# Connector_Board.net
KiCad netlist of a schematic drawn in Altium Designer
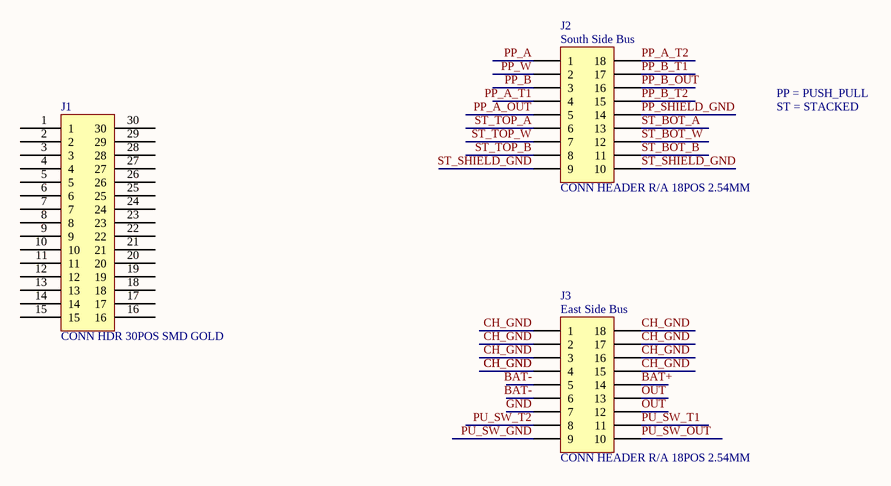
[diagram p0: Connector_Board.SchDoc]

(export (version "E")
  (design (tool "Eeschema 10.0.6"))
  (components
    (comp (ref "J1")
      (value "CONN HDR 30POS SMD GOLD")
      (footprint "DF12(3.0)-30DP")
      (description "30 Position Connector Header, Outer Shroud Contacts Surface Mount Gold")
      (fields (field (name "MANUFACTURER") "Hirose") (field (name "DIGIKEY PART NUMBER") "H11703CT-ND"))
      (libsource (lib "GuitarLibrary") (part "DF12(3.0)-30DP-0.5V(86)"))
    )
    (comp (ref "J2")
      (value "CONN HEADER R/A 18POS 2.54MM")
      (footprint "CONN HEADER R/A 18POS 2.54MM")
      (description "Connector Header Through Hole, Right Angle 18 position 0.100\" (2.54mm)")
      (fields
        (field (name "MANUFACTURER") "Samtec Inc.")
        (field (name "DIGIKEY PART NUMBER") "SAM1041-09-ND")
      )
      (libsource (lib "GuitarLibrary") (part "CONN HEADER R/A 18POS 2.54MM"))
    )
    (comp (ref "J3")
      (value "CONN HEADER R/A 18POS 2.54MM")
      (footprint "CONN HEADER R/A 18POS 2.54MM")
      (description "Connector Header Through Hole, Right Angle 18 position 0.100\" (2.54mm)")
      (fields
        (field (name "MANUFACTURER") "Samtec Inc.")
        (field (name "DIGIKEY PART NUMBER") "SAM1041-09-ND")
      )
      (libsource (lib "GuitarLibrary") (part "CONN HEADER R/A 18POS 2.54MM"))
    )
  )
  (nets
    (net (code "1") (name "/BAT+") (class "Default")
      (node (ref "J3") (pin "14") (pinfunction "14_14") (pintype "passive"))
    )
    (net (code "2") (name "/BAT-") (class "Default")
      (node (ref "J3") (pin "5") (pinfunction "5_5") (pintype "passive"))
      (node (ref "J3") (pin "6") (pinfunction "6_6") (pintype "passive"))
    )
    (net (code "3") (name "/CH_GND") (class "Default")
      (node (ref "J3") (pin "1") (pinfunction "1_1") (pintype "passive"))
      (node (ref "J3") (pin "15") (pinfunction "15_15") (pintype "passive"))
      (node (ref "J3") (pin "16") (pinfunction "16_16") (pintype "passive"))
      (node (ref "J3") (pin "17") (pinfunction "17_17") (pintype "passive"))
      (node (ref "J3") (pin "18") (pinfunction "18_18") (pintype "passive"))
      (node (ref "J3") (pin "2") (pinfunction "2_2") (pintype "passive"))
      (node (ref "J3") (pin "3") (pinfunction "3_3") (pintype "passive"))
      (node (ref "J3") (pin "4") (pinfunction "4_4") (pintype "passive"))
    )
    (net (code "4") (name "/GND") (class "Default")
      (node (ref "J3") (pin "7") (pinfunction "7_7") (pintype "passive"))
    )
    (net (code "5") (name "/OUT") (class "Default")
      (node (ref "J3") (pin "12") (pinfunction "12_12") (pintype "passive"))
      (node (ref "J3") (pin "13") (pinfunction "13_13") (pintype "passive"))
    )
    (net (code "6") (name "/PP_A") (class "Default")
      (node (ref "J2") (pin "1") (pinfunction "1_1") (pintype "passive"))
    )
    (net (code "7") (name "/PP_A_OUT") (class "Default")
      (node (ref "J2") (pin "5") (pinfunction "5_5") (pintype "passive"))
    )
    (net (code "8") (name "/PP_A_T1") (class "Default")
      (node (ref "J2") (pin "4") (pinfunction "4_4") (pintype "passive"))
    )
    (net (code "9") (name "/PP_A_T2") (class "Default")
      (node (ref "J2") (pin "18") (pinfunction "18_18") (pintype "passive"))
    )
    (net (code "10") (name "/PP_B") (class "Default")
      (node (ref "J2") (pin "3") (pinfunction "3_3") (pintype "passive"))
    )
    (net (code "11") (name "/PP_B_OUT") (class "Default")
      (node (ref "J2") (pin "16") (pinfunction "16_16") (pintype "passive"))
    )
    (net (code "12") (name "/PP_B_T1") (class "Default")
      (node (ref "J2") (pin "17") (pinfunction "17_17") (pintype "passive"))
    )
    (net (code "13") (name "/PP_B_T2") (class "Default")
      (node (ref "J2") (pin "15") (pinfunction "15_15") (pintype "passive"))
    )
    (net (code "14") (name "/PP_SHIELD_GND") (class "Default")
      (node (ref "J2") (pin "14") (pinfunction "14_14") (pintype "passive"))
    )
    (net (code "15") (name "/PP_W") (class "Default")
      (node (ref "J2") (pin "2") (pinfunction "2_2") (pintype "passive"))
    )
    (net (code "16") (name "/PU_SW_GND") (class "Default")
      (node (ref "J3") (pin "9") (pinfunction "9_9") (pintype "passive"))
    )
    (net (code "17") (name "/PU_SW_OUT") (class "Default")
      (node (ref "J3") (pin "10") (pinfunction "10_10") (pintype "passive"))
    )
    (net (code "18") (name "/PU_SW_T1") (class "Default")
      (node (ref "J3") (pin "11") (pinfunction "11_11") (pintype "passive"))
    )
    (net (code "19") (name "/PU_SW_T2") (class "Default")
      (node (ref "J3") (pin "8") (pinfunction "8_8") (pintype "passive"))
    )
    (net (code "20") (name "/ST_BOT_A") (class "Default")
      (node (ref "J2") (pin "13") (pinfunction "13_13") (pintype "passive"))
    )
    (net (code "21") (name "/ST_BOT_B") (class "Default")
      (node (ref "J2") (pin "11") (pinfunction "11_11") (pintype "passive"))
    )
    (net (code "22") (name "/ST_BOT_W") (class "Default")
      (node (ref "J2") (pin "12") (pinfunction "12_12") (pintype "passive"))
    )
    (net (code "23") (name "/ST_SHIELD_GND") (class "Default")
      (node (ref "J2") (pin "10") (pinfunction "10_10") (pintype "passive"))
      (node (ref "J2") (pin "9") (pinfunction "9_9") (pintype "passive"))
    )
    (net (code "24") (name "/ST_TOP_A") (class "Default")
      (node (ref "J2") (pin "6") (pinfunction "6_6") (pintype "passive"))
    )
    (net (code "25") (name "/ST_TOP_B") (class "Default")
      (node (ref "J2") (pin "8") (pinfunction "8_8") (pintype "passive"))
    )
    (net (code "26") (name "/ST_TOP_W") (class "Default")
      (node (ref "J2") (pin "7") (pinfunction "7_7") (pintype "passive"))
    )
    (net (code "27") (name "unconnected-(J1-Pad1)") (class "Default")
      (node (ref "J1") (pin "1") (pinfunction "1_1") (pintype "passive"))
    )
    (net (code "28") (name "unconnected-(J1-Pad2)") (class "Default")
      (node (ref "J1") (pin "2") (pinfunction "2_2") (pintype "passive"))
    )
    (net (code "29") (name "unconnected-(J1-Pad3)") (class "Default")
      (node (ref "J1") (pin "3") (pinfunction "3_3") (pintype "passive"))
    )
    (net (code "30") (name "unconnected-(J1-Pad4)") (class "Default")
      (node (ref "J1") (pin "4") (pinfunction "4_4") (pintype "passive"))
    )
    (net (code "31") (name "unconnected-(J1-Pad5)") (class "Default")
      (node (ref "J1") (pin "5") (pinfunction "5_5") (pintype "passive"))
    )
    (net (code "32") (name "unconnected-(J1-Pad6)") (class "Default")
      (node (ref "J1") (pin "6") (pinfunction "6_6") (pintype "passive"))
    )
    (net (code "33") (name "unconnected-(J1-Pad7)") (class "Default")
      (node (ref "J1") (pin "7") (pinfunction "7_7") (pintype "passive"))
    )
    (net (code "34") (name "unconnected-(J1-Pad8)") (class "Default")
      (node (ref "J1") (pin "8") (pinfunction "8_8") (pintype "passive"))
    )
    (net (code "35") (name "unconnected-(J1-Pad9)") (class "Default")
      (node (ref "J1") (pin "9") (pinfunction "9_9") (pintype "passive"))
    )
    (net (code "36") (name "unconnected-(J1-Pad10)") (class "Default")
      (node (ref "J1") (pin "10") (pinfunction "10_10") (pintype "passive"))
    )
    (net (code "37") (name "unconnected-(J1-Pad11)") (class "Default")
      (node (ref "J1") (pin "11") (pinfunction "11_11") (pintype "passive"))
    )
    (net (code "38") (name "unconnected-(J1-Pad12)") (class "Default")
      (node (ref "J1") (pin "12") (pinfunction "12_12") (pintype "passive"))
    )
    (net (code "39") (name "unconnected-(J1-Pad13)") (class "Default")
      (node (ref "J1") (pin "13") (pinfunction "13_13") (pintype "passive"))
    )
    (net (code "40") (name "unconnected-(J1-Pad14)") (class "Default")
      (node (ref "J1") (pin "14") (pinfunction "14_14") (pintype "passive"))
    )
    (net (code "41") (name "unconnected-(J1-Pad15)") (class "Default")
      (node (ref "J1") (pin "15") (pinfunction "15_15") (pintype "passive"))
    )
    (net (code "42") (name "unconnected-(J1-Pad16)") (class "Default")
      (node (ref "J1") (pin "16") (pinfunction "16_16") (pintype "passive"))
    )
    (net (code "43") (name "unconnected-(J1-Pad17)") (class "Default")
      (node (ref "J1") (pin "17") (pinfunction "17_17") (pintype "passive"))
    )
    (net (code "44") (name "unconnected-(J1-Pad18)") (class "Default")
      (node (ref "J1") (pin "18") (pinfunction "18_18") (pintype "passive"))
    )
    (net (code "45") (name "unconnected-(J1-Pad19)") (class "Default")
      (node (ref "J1") (pin "19") (pinfunction "19_19") (pintype "passive"))
    )
    (net (code "46") (name "unconnected-(J1-Pad20)") (class "Default")
      (node (ref "J1") (pin "20") (pinfunction "20_20") (pintype "passive"))
    )
    (net (code "47") (name "unconnected-(J1-Pad21)") (class "Default")
      (node (ref "J1") (pin "21") (pinfunction "21_21") (pintype "passive"))
    )
    (net (code "48") (name "unconnected-(J1-Pad22)") (class "Default")
      (node (ref "J1") (pin "22") (pinfunction "22_22") (pintype "passive"))
    )
    (net (code "49") (name "unconnected-(J1-Pad23)") (class "Default")
      (node (ref "J1") (pin "23") (pinfunction "23_23") (pintype "passive"))
    )
    (net (code "50") (name "unconnected-(J1-Pad24)") (class "Default")
      (node (ref "J1") (pin "24") (pinfunction "24_24") (pintype "passive"))
    )
    (net (code "51") (name "unconnected-(J1-Pad25)") (class "Default")
      (node (ref "J1") (pin "25") (pinfunction "25_25") (pintype "passive"))
    )
    (net (code "52") (name "unconnected-(J1-Pad26)") (class "Default")
      (node (ref "J1") (pin "26") (pinfunction "26_26") (pintype "passive"))
    )
    (net (code "53") (name "unconnected-(J1-Pad27)") (class "Default")
      (node (ref "J1") (pin "27") (pinfunction "27_27") (pintype "passive"))
    )
    (net (code "54") (name "unconnected-(J1-Pad28)") (class "Default")
      (node (ref "J1") (pin "28") (pinfunction "28_28") (pintype "passive"))
    )
    (net (code "55") (name "unconnected-(J1-Pad29)") (class "Default")
      (node (ref "J1") (pin "29") (pinfunction "29_29") (pintype "passive"))
    )
    (net (code "56") (name "unconnected-(J1-Pad30)") (class "Default")
      (node (ref "J1") (pin "30") (pinfunction "30_30") (pintype "passive"))
    )
  )
)
